# valves_card.net
KiCad netlist of a schematic drawn in EAGLE
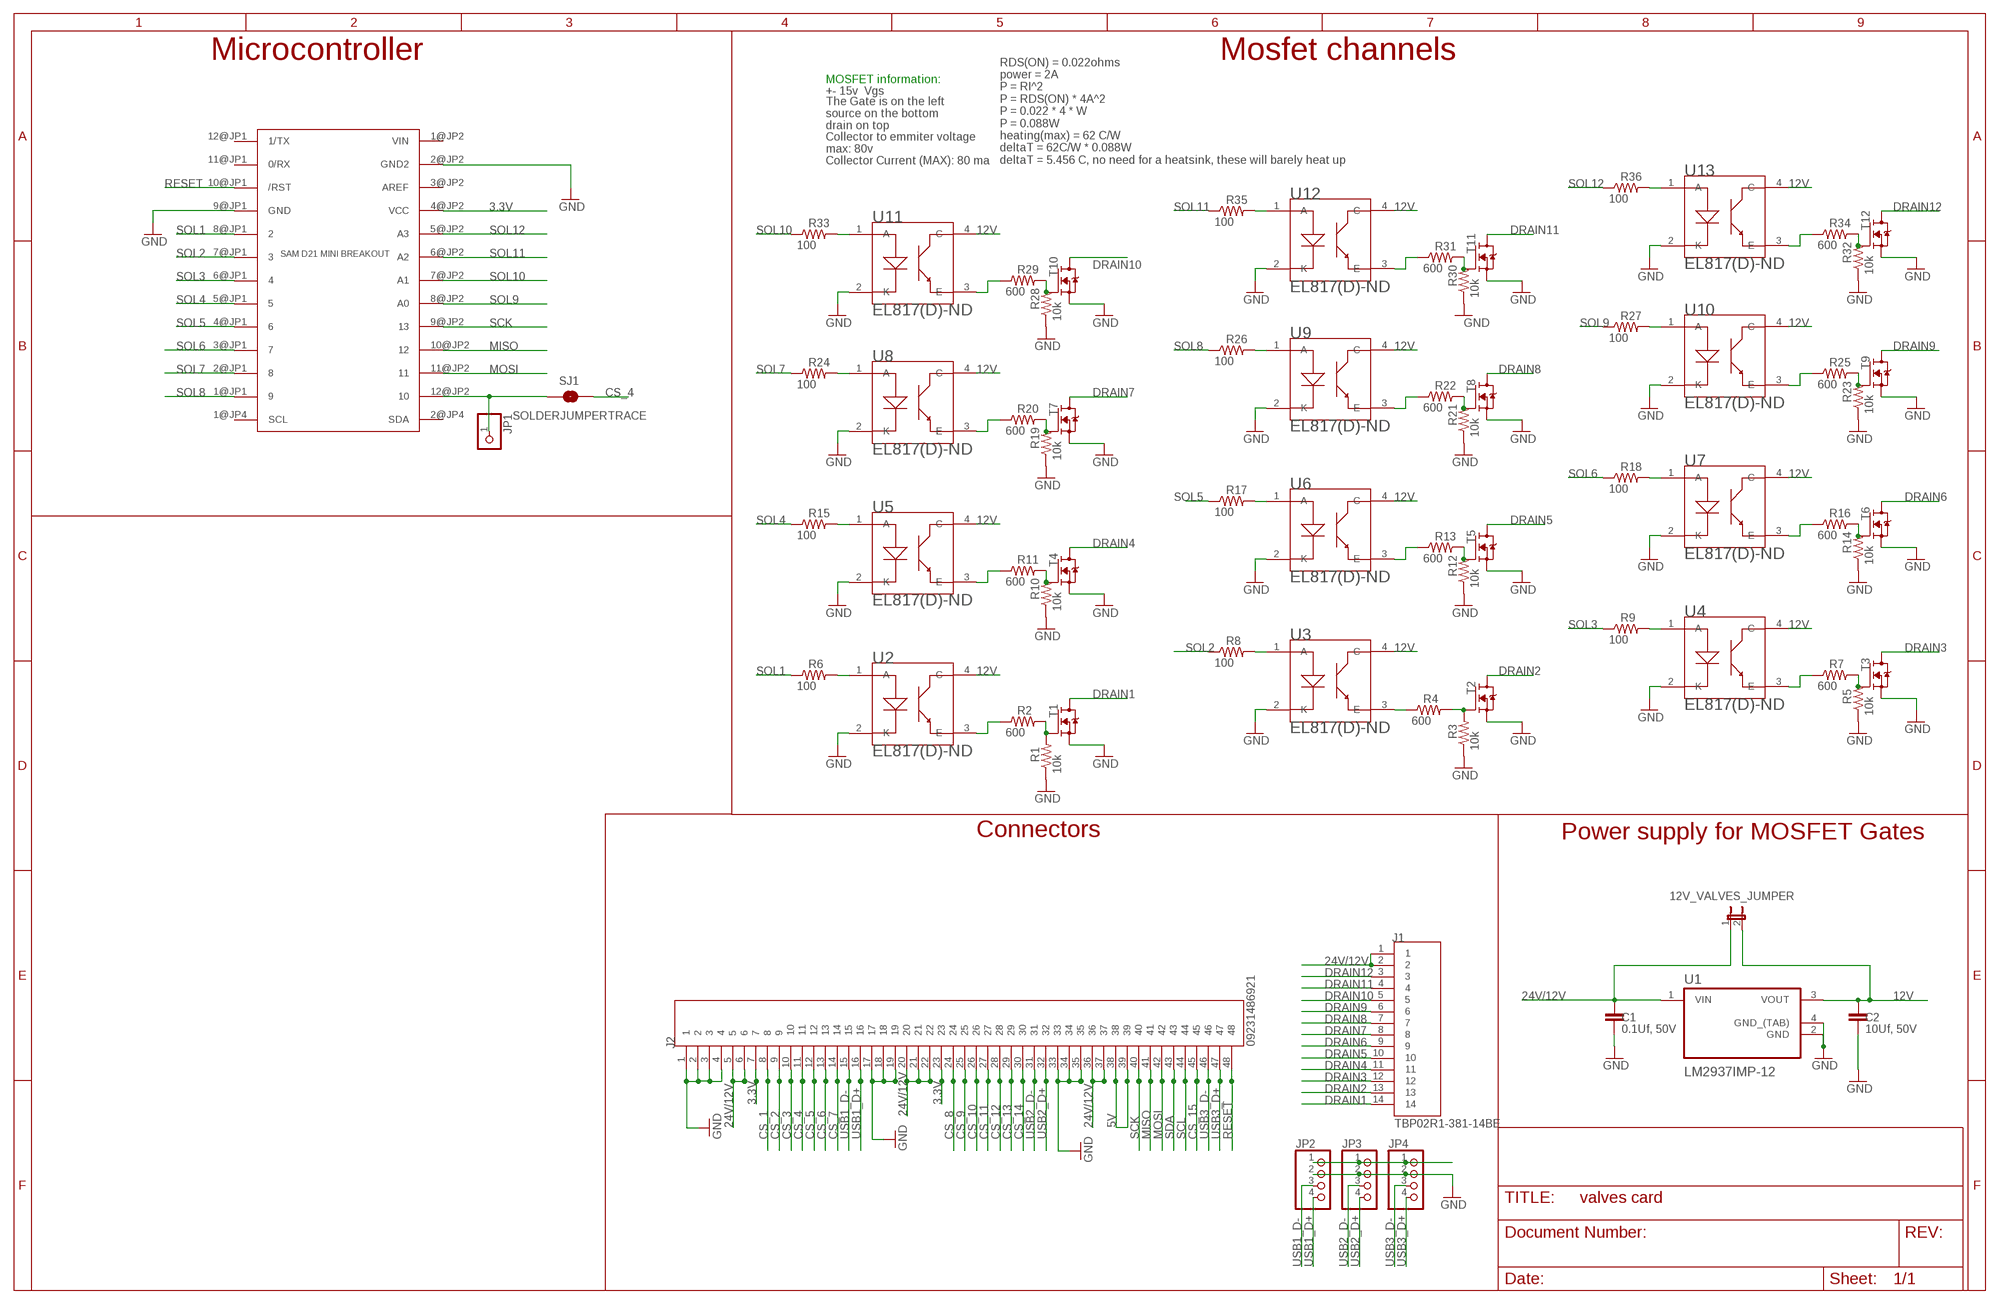
[diagram p0: schematic, sheet 1]

(export (version "E")
  (design (tool "Eeschema 10.0.6"))
  (components
    (comp (ref "12V_VALVES_JUMPER")
      (value "JUMPER-2SMD-NO")
      (footprint "eagle-import:SJ_2S-NO")
      (libsource (lib "eagle-import") (part "JUMPER-2SMD-NO"))
    )
    (comp (ref "C1")
      (value "0.1Uf, 50V")
      (footprint "eagle-import:0805")
      (libsource (lib "eagle-import") (part "CAP0805"))
    )
    (comp (ref "C2")
      (value "10Uf, 50V")
      (footprint "eagle-import:0805")
      (libsource (lib "eagle-import") (part "CAP0805"))
    )
    (comp (ref "J1")
      (value "TBP02R1-381-14BE")
      (footprint "eagle-import:CUI_TBP02R1-381-14BE")
      (libsource (lib "eagle-import") (part "TBP02R1-381-14BE"))
    )
    (comp (ref "J2")
      (value "09231486921")
      (footprint "eagle-import:HARTING_09231486921")
      (libsource (lib "eagle-import") (part "09231486921"))
    )
    (comp (ref "JP1")
      (value "PINHD-1X1")
      (footprint "eagle-import:1X01")
      (libsource (lib "eagle-import") (part "PINHD-1X1"))
    )
    (comp (ref "JP2")
      (value "PINHD-1X4")
      (footprint "eagle-import:1X04")
      (libsource (lib "eagle-import") (part "PINHD-1X4"))
    )
    (comp (ref "JP3")
      (value "PINHD-1X4")
      (footprint "eagle-import:1X04")
      (libsource (lib "eagle-import") (part "PINHD-1X4"))
    )
    (comp (ref "JP4")
      (value "PINHD-1X4")
      (footprint "eagle-import:1X04")
      (libsource (lib "eagle-import") (part "PINHD-1X4"))
    )
    (comp (ref "M2")
      (value "SAM_D21_MINI_BREAKOUT")
      (footprint "eagle-import:JP1_SPARKFUN-SAMD21-MINI-BREAKOUT-V10")
      (libsource (lib "eagle-import") (part "SAM_D21_MINI_BREAKOUT"))
    )
    (comp (ref "R1")
      (value "10k")
      (footprint "eagle-import:0805")
      (libsource (lib "eagle-import") (part "RESISTOR0805-RES"))
    )
    (comp (ref "R2")
      (value "600")
      (footprint "eagle-import:0805")
      (libsource (lib "eagle-import") (part "RESISTOR0805-RES"))
    )
    (comp (ref "R3")
      (value "10k")
      (footprint "eagle-import:0805")
      (libsource (lib "eagle-import") (part "RESISTOR0805-RES"))
    )
    (comp (ref "R4")
      (value "600")
      (footprint "eagle-import:0805")
      (libsource (lib "eagle-import") (part "RESISTOR0805-RES"))
    )
    (comp (ref "R5")
      (value "10k")
      (footprint "eagle-import:0805")
      (libsource (lib "eagle-import") (part "RESISTOR0805-RES"))
    )
    (comp (ref "R6")
      (value "100")
      (footprint "eagle-import:0805")
      (libsource (lib "eagle-import") (part "RESISTOR0805-RES"))
    )
    (comp (ref "R7")
      (value "600")
      (footprint "eagle-import:0805")
      (libsource (lib "eagle-import") (part "RESISTOR0805-RES"))
    )
    (comp (ref "R8")
      (value "100")
      (footprint "eagle-import:0805")
      (libsource (lib "eagle-import") (part "RESISTOR0805-RES"))
    )
    (comp (ref "R9")
      (value "100")
      (footprint "eagle-import:0805")
      (libsource (lib "eagle-import") (part "RESISTOR0805-RES"))
    )
    (comp (ref "R10")
      (value "10k")
      (footprint "eagle-import:0805")
      (libsource (lib "eagle-import") (part "RESISTOR0805-RES"))
    )
    (comp (ref "R11")
      (value "600")
      (footprint "eagle-import:0805")
      (libsource (lib "eagle-import") (part "RESISTOR0805-RES"))
    )
    (comp (ref "R12")
      (value "10k")
      (footprint "eagle-import:0805")
      (libsource (lib "eagle-import") (part "RESISTOR0805-RES"))
    )
    (comp (ref "R13")
      (value "600")
      (footprint "eagle-import:0805")
      (libsource (lib "eagle-import") (part "RESISTOR0805-RES"))
    )
    (comp (ref "R14")
      (value "10k")
      (footprint "eagle-import:0805")
      (libsource (lib "eagle-import") (part "RESISTOR0805-RES"))
    )
    (comp (ref "R15")
      (value "100")
      (footprint "eagle-import:0805")
      (libsource (lib "eagle-import") (part "RESISTOR0805-RES"))
    )
    (comp (ref "R16")
      (value "600")
      (footprint "eagle-import:0805")
      (libsource (lib "eagle-import") (part "RESISTOR0805-RES"))
    )
    (comp (ref "R17")
      (value "100")
      (footprint "eagle-import:0805")
      (libsource (lib "eagle-import") (part "RESISTOR0805-RES"))
    )
    (comp (ref "R18")
      (value "100")
      (footprint "eagle-import:0805")
      (libsource (lib "eagle-import") (part "RESISTOR0805-RES"))
    )
    (comp (ref "R19")
      (value "10k")
      (footprint "eagle-import:0805")
      (libsource (lib "eagle-import") (part "RESISTOR0805-RES"))
    )
    (comp (ref "R20")
      (value "600")
      (footprint "eagle-import:0805")
      (libsource (lib "eagle-import") (part "RESISTOR0805-RES"))
    )
    (comp (ref "R21")
      (value "10k")
      (footprint "eagle-import:0805")
      (libsource (lib "eagle-import") (part "RESISTOR0805-RES"))
    )
    (comp (ref "R22")
      (value "600")
      (footprint "eagle-import:0805")
      (libsource (lib "eagle-import") (part "RESISTOR0805-RES"))
    )
    (comp (ref "R23")
      (value "10k")
      (footprint "eagle-import:0805")
      (libsource (lib "eagle-import") (part "RESISTOR0805-RES"))
    )
    (comp (ref "R24")
      (value "100")
      (footprint "eagle-import:0805")
      (libsource (lib "eagle-import") (part "RESISTOR0805-RES"))
    )
    (comp (ref "R25")
      (value "600")
      (footprint "eagle-import:0805")
      (libsource (lib "eagle-import") (part "RESISTOR0805-RES"))
    )
    (comp (ref "R26")
      (value "100")
      (footprint "eagle-import:0805")
      (libsource (lib "eagle-import") (part "RESISTOR0805-RES"))
    )
    (comp (ref "R27")
      (value "100")
      (footprint "eagle-import:0805")
      (libsource (lib "eagle-import") (part "RESISTOR0805-RES"))
    )
    (comp (ref "R28")
      (value "10k")
      (footprint "eagle-import:0805")
      (libsource (lib "eagle-import") (part "RESISTOR0805-RES"))
    )
    (comp (ref "R29")
      (value "600")
      (footprint "eagle-import:0805")
      (libsource (lib "eagle-import") (part "RESISTOR0805-RES"))
    )
    (comp (ref "R30")
      (value "10k")
      (footprint "eagle-import:0805")
      (libsource (lib "eagle-import") (part "RESISTOR0805-RES"))
    )
    (comp (ref "R31")
      (value "600")
      (footprint "eagle-import:0805")
      (libsource (lib "eagle-import") (part "RESISTOR0805-RES"))
    )
    (comp (ref "R32")
      (value "10k")
      (footprint "eagle-import:0805")
      (libsource (lib "eagle-import") (part "RESISTOR0805-RES"))
    )
    (comp (ref "R33")
      (value "100")
      (footprint "eagle-import:0805")
      (libsource (lib "eagle-import") (part "RESISTOR0805-RES"))
    )
    (comp (ref "R34")
      (value "600")
      (footprint "eagle-import:0805")
      (libsource (lib "eagle-import") (part "RESISTOR0805-RES"))
    )
    (comp (ref "R35")
      (value "100")
      (footprint "eagle-import:0805")
      (libsource (lib "eagle-import") (part "RESISTOR0805-RES"))
    )
    (comp (ref "R36")
      (value "100")
      (footprint "eagle-import:0805")
      (libsource (lib "eagle-import") (part "RESISTOR0805-RES"))
    )
    (comp (ref "SJ1")
      (value "SOLDERJUMPERTRACE")
      (footprint "eagle-import:SJ_2S-TRACE")
      (libsource (lib "eagle-import") (part "SOLDERJUMPERTRACE"))
    )
    (comp (ref "T1")
      (value "IRLZ44NSTRLPBF")
      (footprint "eagle-import:DPAK_TO252")
      (libsource (lib "eagle-import") (part "BUK9214-30A-118-DPAK"))
    )
    (comp (ref "T2")
      (value "IRLZ44NSTRLPBF")
      (footprint "eagle-import:DPAK_TO252")
      (libsource (lib "eagle-import") (part "BUK9214-30A-118-DPAK"))
    )
    (comp (ref "T3")
      (value "IRLZ44NSTRLPBF")
      (footprint "eagle-import:DPAK_TO252")
      (libsource (lib "eagle-import") (part "BUK9214-30A-118-DPAK"))
    )
    (comp (ref "T4")
      (value "IRLZ44NSTRLPBF")
      (footprint "eagle-import:DPAK_TO252")
      (libsource (lib "eagle-import") (part "BUK9214-30A-118-DPAK"))
    )
    (comp (ref "T5")
      (value "IRLZ44NSTRLPBF")
      (footprint "eagle-import:DPAK_TO252")
      (libsource (lib "eagle-import") (part "BUK9214-30A-118-DPAK"))
    )
    (comp (ref "T6")
      (value "IRLZ44NSTRLPBF")
      (footprint "eagle-import:DPAK_TO252")
      (libsource (lib "eagle-import") (part "BUK9214-30A-118-DPAK"))
    )
    (comp (ref "T7")
      (value "IRLZ44NSTRLPBF")
      (footprint "eagle-import:DPAK_TO252")
      (libsource (lib "eagle-import") (part "BUK9214-30A-118-DPAK"))
    )
    (comp (ref "T8")
      (value "IRLZ44NSTRLPBF")
      (footprint "eagle-import:DPAK_TO252")
      (libsource (lib "eagle-import") (part "BUK9214-30A-118-DPAK"))
    )
    (comp (ref "T9")
      (value "IRLZ44NSTRLPBF")
      (footprint "eagle-import:DPAK_TO252")
      (libsource (lib "eagle-import") (part "BUK9214-30A-118-DPAK"))
    )
    (comp (ref "T10")
      (value "IRLZ44NSTRLPBF")
      (footprint "eagle-import:DPAK_TO252")
      (libsource (lib "eagle-import") (part "BUK9214-30A-118-DPAK"))
    )
    (comp (ref "T11")
      (value "IRLZ44NSTRLPBF")
      (footprint "eagle-import:DPAK_TO252")
      (libsource (lib "eagle-import") (part "BUK9214-30A-118-DPAK"))
    )
    (comp (ref "T12")
      (value "IRLZ44NSTRLPBF")
      (footprint "eagle-import:DPAK_TO252")
      (libsource (lib "eagle-import") (part "BUK9214-30A-118-DPAK"))
    )
    (comp (ref "U1")
      (value "LM2937IMP-12")
      (footprint "eagle-import:SOT230P700X180-4N")
      (libsource (lib "eagle-import") (part "LM2937IMP-12"))
    )
    (comp (ref "U2")
      (value "EL817(D)-ND")
      (footprint "eagle-import:DIP4")
      (libsource (lib "eagle-import") (part "EL817(D)"))
    )
    (comp (ref "U3")
      (value "EL817(D)-ND")
      (footprint "eagle-import:DIP4")
      (libsource (lib "eagle-import") (part "EL817(D)"))
    )
    (comp (ref "U4")
      (value "EL817(D)-ND")
      (footprint "eagle-import:DIP4")
      (libsource (lib "eagle-import") (part "EL817(D)"))
    )
    (comp (ref "U5")
      (value "EL817(D)-ND")
      (footprint "eagle-import:DIP4")
      (libsource (lib "eagle-import") (part "EL817(D)"))
    )
    (comp (ref "U6")
      (value "EL817(D)-ND")
      (footprint "eagle-import:DIP4")
      (libsource (lib "eagle-import") (part "EL817(D)"))
    )
    (comp (ref "U7")
      (value "EL817(D)-ND")
      (footprint "eagle-import:DIP4")
      (libsource (lib "eagle-import") (part "EL817(D)"))
    )
    (comp (ref "U8")
      (value "EL817(D)-ND")
      (footprint "eagle-import:DIP4")
      (libsource (lib "eagle-import") (part "EL817(D)"))
    )
    (comp (ref "U9")
      (value "EL817(D)-ND")
      (footprint "eagle-import:DIP4")
      (libsource (lib "eagle-import") (part "EL817(D)"))
    )
    (comp (ref "U10")
      (value "EL817(D)-ND")
      (footprint "eagle-import:DIP4")
      (libsource (lib "eagle-import") (part "EL817(D)"))
    )
    (comp (ref "U11")
      (value "EL817(D)-ND")
      (footprint "eagle-import:DIP4")
      (libsource (lib "eagle-import") (part "EL817(D)"))
    )
    (comp (ref "U12")
      (value "EL817(D)-ND")
      (footprint "eagle-import:DIP4")
      (libsource (lib "eagle-import") (part "EL817(D)"))
    )
    (comp (ref "U13")
      (value "EL817(D)-ND")
      (footprint "eagle-import:DIP4")
      (libsource (lib "eagle-import") (part "EL817(D)"))
    )
  )
  (nets
    (net (code "1") (name "/3.3V") (class "Default")
      (node (ref "J2") (pin "23") (pinfunction "23_23") (pintype "passive"))
      (node (ref "J2") (pin "7") (pinfunction "7_7") (pintype "passive"))
      (node (ref "M2") (pin "4@JP2") (pinfunction "VCC_4@JP2") (pintype "power_in"))
    )
    (net (code "2") (name "/5V") (class "Default")
      (node (ref "J2") (pin "38") (pinfunction "38_38") (pintype "passive"))
      (node (ref "J2") (pin "39") (pinfunction "39_39") (pintype "passive"))
      (node (ref "JP2") (pin "1") (pinfunction "1_1") (pintype "passive"))
      (node (ref "JP3") (pin "1") (pinfunction "1_1") (pintype "passive"))
      (node (ref "JP4") (pin "1") (pinfunction "1_1") (pintype "passive"))
    )
    (net (code "3") (name "/12V") (class "Default")
      (node (ref "12V_VALVES_JUMPER") (pin "2") (pinfunction "2_2") (pintype "passive"))
      (node (ref "C2") (pin "1") (pinfunction "1_1") (pintype "passive"))
      (node (ref "U1") (pin "3") (pinfunction "VOUT_3") (pintype "output"))
      (node (ref "U10") (pin "4") (pinfunction "C_4") (pintype "passive"))
      (node (ref "U11") (pin "4") (pinfunction "C_4") (pintype "passive"))
      (node (ref "U12") (pin "4") (pinfunction "C_4") (pintype "passive"))
      (node (ref "U13") (pin "4") (pinfunction "C_4") (pintype "passive"))
      (node (ref "U2") (pin "4") (pinfunction "C_4") (pintype "passive"))
      (node (ref "U3") (pin "4") (pinfunction "C_4") (pintype "passive"))
      (node (ref "U4") (pin "4") (pinfunction "C_4") (pintype "passive"))
      (node (ref "U5") (pin "4") (pinfunction "C_4") (pintype "passive"))
      (node (ref "U6") (pin "4") (pinfunction "C_4") (pintype "passive"))
      (node (ref "U7") (pin "4") (pinfunction "C_4") (pintype "passive"))
      (node (ref "U8") (pin "4") (pinfunction "C_4") (pintype "passive"))
      (node (ref "U9") (pin "4") (pinfunction "C_4") (pintype "passive"))
    )
    (net (code "4") (name "/24V{slash}12V") (class "Default")
      (node (ref "12V_VALVES_JUMPER") (pin "1") (pinfunction "1_1") (pintype "passive"))
      (node (ref "C1") (pin "1") (pinfunction "1_1") (pintype "passive"))
      (node (ref "J1") (pin "1") (pinfunction "1_1") (pintype "passive"))
      (node (ref "J1") (pin "2") (pinfunction "2_2") (pintype "passive"))
      (node (ref "J2") (pin "20") (pinfunction "20_20") (pintype "passive"))
      (node (ref "J2") (pin "21") (pinfunction "21_21") (pintype "passive"))
      (node (ref "J2") (pin "22") (pinfunction "22_22") (pintype "passive"))
      (node (ref "J2") (pin "36") (pinfunction "36_36") (pintype "passive"))
      (node (ref "J2") (pin "37") (pinfunction "37_37") (pintype "passive"))
      (node (ref "J2") (pin "5") (pinfunction "5_5") (pintype "passive"))
      (node (ref "J2") (pin "6") (pinfunction "6_6") (pintype "passive"))
      (node (ref "U1") (pin "1") (pinfunction "VIN_1") (pintype "input"))
    )
    (net (code "5") (name "/AREF") (class "Default")
      (node (ref "M2") (pin "3@JP2") (pinfunction "AREF_3@JP2") (pintype "power_in"))
    )
    (net (code "6") (name "/CS_1") (class "Default")
      (node (ref "J2") (pin "8") (pinfunction "8_8") (pintype "passive"))
    )
    (net (code "7") (name "/CS_2") (class "Default")
      (node (ref "J2") (pin "9") (pinfunction "9_9") (pintype "passive"))
    )
    (net (code "8") (name "/CS_3") (class "Default")
      (node (ref "J2") (pin "10") (pinfunction "10_10") (pintype "passive"))
    )
    (net (code "9") (name "/CS_4") (class "Default")
      (node (ref "J2") (pin "11") (pinfunction "11_11") (pintype "passive"))
      (node (ref "SJ1") (pin "2") (pinfunction "2_2") (pintype "passive"))
    )
    (net (code "10") (name "/CS_5") (class "Default")
      (node (ref "J2") (pin "12") (pinfunction "12_12") (pintype "passive"))
    )
    (net (code "11") (name "/CS_6") (class "Default")
      (node (ref "J2") (pin "13") (pinfunction "13_13") (pintype "passive"))
    )
    (net (code "12") (name "/CS_7") (class "Default")
      (node (ref "J2") (pin "14") (pinfunction "14_14") (pintype "passive"))
    )
    (net (code "13") (name "/CS_8") (class "Default")
      (node (ref "J2") (pin "24") (pinfunction "24_24") (pintype "passive"))
    )
    (net (code "14") (name "/CS_9") (class "Default")
      (node (ref "J2") (pin "25") (pinfunction "25_25") (pintype "passive"))
    )
    (net (code "15") (name "/CS_10") (class "Default")
      (node (ref "J2") (pin "26") (pinfunction "26_26") (pintype "passive"))
    )
    (net (code "16") (name "/CS_11") (class "Default")
      (node (ref "J2") (pin "27") (pinfunction "27_27") (pintype "passive"))
    )
    (net (code "17") (name "/CS_12") (class "Default")
      (node (ref "J2") (pin "28") (pinfunction "28_28") (pintype "passive"))
    )
    (net (code "18") (name "/CS_13") (class "Default")
      (node (ref "J2") (pin "29") (pinfunction "29_29") (pintype "passive"))
    )
    (net (code "19") (name "/CS_14") (class "Default")
      (node (ref "J2") (pin "30") (pinfunction "30_30") (pintype "passive"))
    )
    (net (code "20") (name "/CS_15") (class "Default")
      (node (ref "J2") (pin "45") (pinfunction "45_45") (pintype "passive"))
    )
    (net (code "21") (name "/DRAIN1") (class "Default")
      (node (ref "J1") (pin "14") (pinfunction "14_14") (pintype "passive"))
      (node (ref "T1") (pin "2") (pinfunction "D_2") (pintype "passive"))
    )
    (net (code "22") (name "/DRAIN2") (class "Default")
      (node (ref "J1") (pin "13") (pinfunction "13_13") (pintype "passive"))
      (node (ref "T2") (pin "2") (pinfunction "D_2") (pintype "passive"))
    )
    (net (code "23") (name "/DRAIN3") (class "Default")
      (node (ref "J1") (pin "12") (pinfunction "12_12") (pintype "passive"))
      (node (ref "T3") (pin "2") (pinfunction "D_2") (pintype "passive"))
    )
    (net (code "24") (name "/DRAIN4") (class "Default")
      (node (ref "J1") (pin "11") (pinfunction "11_11") (pintype "passive"))
      (node (ref "T4") (pin "2") (pinfunction "D_2") (pintype "passive"))
    )
    (net (code "25") (name "/DRAIN5") (class "Default")
      (node (ref "J1") (pin "10") (pinfunction "10_10") (pintype "passive"))
      (node (ref "T5") (pin "2") (pinfunction "D_2") (pintype "passive"))
    )
    (net (code "26") (name "/DRAIN6") (class "Default")
      (node (ref "J1") (pin "9") (pinfunction "9_9") (pintype "passive"))
      (node (ref "T6") (pin "2") (pinfunction "D_2") (pintype "passive"))
    )
    (net (code "27") (name "/DRAIN7") (class "Default")
      (node (ref "J1") (pin "8") (pinfunction "8_8") (pintype "passive"))
      (node (ref "T7") (pin "2") (pinfunction "D_2") (pintype "passive"))
    )
    (net (code "28") (name "/DRAIN8") (class "Default")
      (node (ref "J1") (pin "7") (pinfunction "7_7") (pintype "passive"))
      (node (ref "T8") (pin "2") (pinfunction "D_2") (pintype "passive"))
    )
    (net (code "29") (name "/DRAIN9") (class "Default")
      (node (ref "J1") (pin "6") (pinfunction "6_6") (pintype "passive"))
      (node (ref "T9") (pin "2") (pinfunction "D_2") (pintype "passive"))
    )
    (net (code "30") (name "/DRAIN10") (class "Default")
      (node (ref "J1") (pin "5") (pinfunction "5_5") (pintype "passive"))
      (node (ref "T10") (pin "2") (pinfunction "D_2") (pintype "passive"))
    )
    (net (code "31") (name "/DRAIN11") (class "Default")
      (node (ref "J1") (pin "4") (pinfunction "4_4") (pintype "passive"))
      (node (ref "T11") (pin "2") (pinfunction "D_2") (pintype "passive"))
    )
    (net (code "32") (name "/DRAIN12") (class "Default")
      (node (ref "J1") (pin "3") (pinfunction "3_3") (pintype "passive"))
      (node (ref "T12") (pin "2") (pinfunction "D_2") (pintype "passive"))
    )
    (net (code "33") (name "/MISO") (class "Default")
      (node (ref "J2") (pin "41") (pinfunction "41_41") (pintype "passive"))
      (node (ref "M2") (pin "10@JP2") (pinfunction "12_10@JP2") (pintype "bidirectional"))
    )
    (net (code "34") (name "/MOSI") (class "Default")
      (node (ref "J2") (pin "42") (pinfunction "42_42") (pintype "passive"))
      (node (ref "M2") (pin "11@JP2") (pinfunction "11_11@JP2") (pintype "bidirectional"))
    )
    (net (code "35") (name "/RESET") (class "Default")
      (node (ref "J2") (pin "48") (pinfunction "48_48") (pintype "passive"))
      (node (ref "M2") (pin "10@JP1") (pinfunction "/RST_10@JP1") (pintype "input"))
    )
    (net (code "36") (name "/SCK") (class "Default")
      (node (ref "J2") (pin "40") (pinfunction "40_40") (pintype "passive"))
      (node (ref "M2") (pin "9@JP2") (pinfunction "13_9@JP2") (pintype "bidirectional"))
    )
    (net (code "37") (name "/SCL") (class "Default")
      (node (ref "J2") (pin "44") (pinfunction "44_44") (pintype "passive"))
    )
    (net (code "38") (name "/SDA") (class "Default")
      (node (ref "J2") (pin "43") (pinfunction "43_43") (pintype "passive"))
    )
    (net (code "39") (name "/SOL1") (class "Default")
      (node (ref "M2") (pin "8@JP1") (pinfunction "2_8@JP1") (pintype "bidirectional"))
      (node (ref "R6") (pin "1") (pinfunction "1_1") (pintype "passive"))
    )
    (net (code "40") (name "/SOL2") (class "Default")
      (node (ref "M2") (pin "7@JP1") (pinfunction "3_7@JP1") (pintype "bidirectional"))
      (node (ref "R8") (pin "1") (pinfunction "1_1") (pintype "passive"))
    )
    (net (code "41") (name "/SOL3") (class "Default")
      (node (ref "M2") (pin "6@JP1") (pinfunction "4_6@JP1") (pintype "bidirectional"))
      (node (ref "R9") (pin "1") (pinfunction "1_1") (pintype "passive"))
    )
    (net (code "42") (name "/SOL4") (class "Default")
      (node (ref "M2") (pin "5@JP1") (pinfunction "5_5@JP1") (pintype "bidirectional"))
      (node (ref "R15") (pin "1") (pinfunction "1_1") (pintype "passive"))
    )
    (net (code "43") (name "/SOL5") (class "Default")
      (node (ref "M2") (pin "4@JP1") (pinfunction "6_4@JP1") (pintype "bidirectional"))
      (node (ref "R17") (pin "1") (pinfunction "1_1") (pintype "passive"))
    )
    (net (code "44") (name "/SOL6") (class "Default")
      (node (ref "M2") (pin "3@JP1") (pinfunction "7_3@JP1") (pintype "bidirectional"))
      (node (ref "R18") (pin "1") (pinfunction "1_1") (pintype "passive"))
    )
    (net (code "45") (name "/SOL7") (class "Default")
      (node (ref "M2") (pin "2@JP1") (pinfunction "8_2@JP1") (pintype "bidirectional"))
      (node (ref "R24") (pin "1") (pinfunction "1_1") (pintype "passive"))
    )
    (net (code "46") (name "/SOL8") (class "Default")
      (node (ref "M2") (pin "1@JP1") (pinfunction "9_1@JP1") (pintype "bidirectional"))
      (node (ref "R26") (pin "1") (pinfunction "1_1") (pintype "passive"))
    )
    (net (code "47") (name "/SOL9") (class "Default")
      (node (ref "M2") (pin "8@JP2") (pinfunction "A0_8@JP2") (pintype "bidirectional"))
      (node (ref "R27") (pin "1") (pinfunction "1_1") (pintype "passive"))
    )
    (net (code "48") (name "/SOL10") (class "Default")
      (node (ref "M2") (pin "7@JP2") (pinfunction "A1_7@JP2") (pintype "bidirectional"))
      (node (ref "R33") (pin "1") (pinfunction "1_1") (pintype "passive"))
    )
    (net (code "49") (name "/SOL11") (class "Default")
      (node (ref "M2") (pin "6@JP2") (pinfunction "A2_6@JP2") (pintype "bidirectional"))
      (node (ref "R35") (pin "1") (pinfunction "1_1") (pintype "passive"))
    )
    (net (code "50") (name "/SOL12") (class "Default")
      (node (ref "M2") (pin "5@JP2") (pinfunction "A3_5@JP2") (pintype "bidirectional"))
      (node (ref "R36") (pin "1") (pinfunction "1_1") (pintype "passive"))
    )
    (net (code "51") (name "/USB1_D+") (class "Default")
      (node (ref "J2") (pin "16") (pinfunction "16_16") (pintype "passive"))
      (node (ref "JP2") (pin "4") (pinfunction "4_4") (pintype "passive"))
    )
    (net (code "52") (name "/USB1_D-") (class "Default")
      (node (ref "J2") (pin "15") (pinfunction "15_15") (pintype "passive"))
      (node (ref "JP2") (pin "3") (pinfunction "3_3") (pintype "passive"))
    )
    (net (code "53") (name "/USB2_D+") (class "Default")
      (node (ref "J2") (pin "32") (pinfunction "32_32") (pintype "passive"))
      (node (ref "JP3") (pin "4") (pinfunction "4_4") (pintype "passive"))
    )
    (net (code "54") (name "/USB2_D-") (class "Default")
      (node (ref "J2") (pin "31") (pinfunction "31_31") (pintype "passive"))
      (node (ref "JP3") (pin "3") (pinfunction "3_3") (pintype "passive"))
    )
    (net (code "55") (name "/USB3_D+") (class "Default")
      (node (ref "J2") (pin "47") (pinfunction "47_47") (pintype "passive"))
      (node (ref "JP4") (pin "4") (pinfunction "4_4") (pintype "passive"))
    )
    (net (code "56") (name "/USB3_D-") (class "Default")
      (node (ref "J2") (pin "46") (pinfunction "46_46") (pintype "passive"))
      (node (ref "JP4") (pin "3") (pinfunction "3_3") (pintype "passive"))
    )
    (net (code "57") (name "/VIN") (class "Default")
      (node (ref "M2") (pin "1@JP2") (pinfunction "VIN_1@JP2") (pintype "power_in"))
    )
    (net (code "58") (name "GND") (class "Default")
      (node (ref "C1") (pin "2") (pinfunction "2_2") (pintype "passive"))
      (node (ref "C2") (pin "2") (pinfunction "2_2") (pintype "passive"))
      (node (ref "J2") (pin "1") (pinfunction "1_1") (pintype "passive"))
      (node (ref "J2") (pin "17") (pinfunction "17_17") (pintype "passive"))
      (node (ref "J2") (pin "18") (pinfunction "18_18") (pintype "passive"))
      (node (ref "J2") (pin "19") (pinfunction "19_19") (pintype "passive"))
      (node (ref "J2") (pin "2") (pinfunction "2_2") (pintype "passive"))
      (node (ref "J2") (pin "3") (pinfunction "3_3") (pintype "passive"))
      (node (ref "J2") (pin "33") (pinfunction "33_33") (pintype "passive"))
      (node (ref "J2") (pin "34") (pinfunction "34_34") (pintype "passive"))
      (node (ref "J2") (pin "35") (pinfunction "35_35") (pintype "passive"))
      (node (ref "J2") (pin "4") (pinfunction "4_4") (pintype "passive"))
      (node (ref "JP2") (pin "2") (pinfunction "2_2") (pintype "passive"))
      (node (ref "JP3") (pin "2") (pinfunction "2_2") (pintype "passive"))
      (node (ref "JP4") (pin "2") (pinfunction "2_2") (pintype "passive"))
      (node (ref "M2") (pin "2@JP2") (pinfunction "GND2_2@JP2") (pintype "power_in"))
      (node (ref "M2") (pin "9@JP1") (pinfunction "GND_9@JP1") (pintype "power_in"))
      (node (ref "R1") (pin "1") (pinfunction "1_1") (pintype "passive"))
      (node (ref "R10") (pin "1") (pinfunction "1_1") (pintype "passive"))
      (node (ref "R12") (pin "1") (pinfunction "1_1") (pintype "passive"))
      (node (ref "R14") (pin "1") (pinfunction "1_1") (pintype "passive"))
      (node (ref "R19") (pin "1") (pinfunction "1_1") (pintype "passive"))
      (node (ref "R21") (pin "1") (pinfunction "1_1") (pintype "passive"))
      (node (ref "R23") (pin "1") (pinfunction "1_1") (pintype "passive"))
      (node (ref "R28") (pin "1") (pinfunction "1_1") (pintype "passive"))
      (node (ref "R3") (pin "1") (pinfunction "1_1") (pintype "passive"))
      (node (ref "R30") (pin "1") (pinfunction "1_1") (pintype "passive"))
      (node (ref "R32") (pin "1") (pinfunction "1_1") (pintype "passive"))
      (node (ref "R5") (pin "1") (pinfunction "1_1") (pintype "passive"))
      (node (ref "T1") (pin "3") (pinfunction "S_3") (pintype "passive"))
      (node (ref "T10") (pin "3") (pinfunction "S_3") (pintype "passive"))
      (node (ref "T11") (pin "3") (pinfunction "S_3") (pintype "passive"))
      (node (ref "T12") (pin "3") (pinfunction "S_3") (pintype "passive"))
      (node (ref "T2") (pin "3") (pinfunction "S_3") (pintype "passive"))
      (node (ref "T3") (pin "3") (pinfunction "S_3") (pintype "passive"))
      (node (ref "T4") (pin "3") (pinfunction "S_3") (pintype "passive"))
      (node (ref "T5") (pin "3") (pinfunction "S_3") (pintype "passive"))
      (node (ref "T6") (pin "3") (pinfunction "S_3") (pintype "passive"))
      (node (ref "T7") (pin "3") (pinfunction "S_3") (pintype "passive"))
      (node (ref "T8") (pin "3") (pinfunction "S_3") (pintype "passive"))
      (node (ref "T9") (pin "3") (pinfunction "S_3") (pintype "passive"))
      (node (ref "U1") (pin "2") (pinfunction "GND_2") (pintype "power_in"))
      (node (ref "U1") (pin "4") (pinfunction "GND_(TAB)_4") (pintype "power_in"))
      (node (ref "U10") (pin "2") (pinfunction "K_2") (pintype "passive"))
      (node (ref "U11") (pin "2") (pinfunction "K_2") (pintype "passive"))
      (node (ref "U12") (pin "2") (pinfunction "K_2") (pintype "passive"))
      (node (ref "U13") (pin "2") (pinfunction "K_2") (pintype "passive"))
      (node (ref "U2") (pin "2") (pinfunction "K_2") (pintype "passive"))
      (node (ref "U3") (pin "2") (pinfunction "K_2") (pintype "passive"))
      (node (ref "U4") (pin "2") (pinfunction "K_2") (pintype "passive"))
      (node (ref "U5") (pin "2") (pinfunction "K_2") (pintype "passive"))
      (node (ref "U6") (pin "2") (pinfunction "K_2") (pintype "passive"))
      (node (ref "U7") (pin "2") (pinfunction "K_2") (pintype "passive"))
      (node (ref "U8") (pin "2") (pinfunction "K_2") (pintype "passive"))
      (node (ref "U9") (pin "2") (pinfunction "K_2") (pintype "passive"))
    )
    (net (code "59") (name "Net-(M2-10)") (class "Default")
      (node (ref "JP1") (pin "1") (pinfunction "1_1") (pintype "passive"))
      (node (ref "M2") (pin "12@JP2") (pinfunction "10_12@JP2") (pintype "bidirectional"))
      (node (ref "SJ1") (pin "1") (pinfunction "1_1") (pintype "passive"))
    )
    (net (code "60") (name "Net-(T1-G)") (class "Default")
      (node (ref "R1") (pin "2") (pinfunction "2_2") (pintype "passive"))
      (node (ref "R2") (pin "2") (pinfunction "2_2") (pintype "passive"))
      (node (ref "T1") (pin "1") (pinfunction "G_1") (pintype "passive"))
    )
    (net (code "61") (name "Net-(T2-G)") (class "Default")
      (node (ref "R3") (pin "2") (pinfunction "2_2") (pintype "passive"))
      (node (ref "R4") (pin "2") (pinfunction "2_2") (pintype "passive"))
      (node (ref "T2") (pin "1") (pinfunction "G_1") (pintype "passive"))
    )
    (net (code "62") (name "Net-(T3-G)") (class "Default")
      (node (ref "R5") (pin "2") (pinfunction "2_2") (pintype "passive"))
      (node (ref "R7") (pin "2") (pinfunction "2_2") (pintype "passive"))
      (node (ref "T3") (pin "1") (pinfunction "G_1") (pintype "passive"))
    )
    (net (code "63") (name "Net-(T4-G)") (class "Default")
      (node (ref "R10") (pin "2") (pinfunction "2_2") (pintype "passive"))
      (node (ref "R11") (pin "2") (pinfunction "2_2") (pintype "passive"))
      (node (ref "T4") (pin "1") (pinfunction "G_1") (pintype "passive"))
    )
    (net (code "64") (name "Net-(T5-G)") (class "Default")
      (node (ref "R12") (pin "2") (pinfunction "2_2") (pintype "passive"))
      (node (ref "R13") (pin "2") (pinfunction "2_2") (pintype "passive"))
      (node (ref "T5") (pin "1") (pinfunction "G_1") (pintype "passive"))
    )
    (net (code "65") (name "Net-(T6-G)") (class "Default")
      (node (ref "R14") (pin "2") (pinfunction "2_2") (pintype "passive"))
      (node (ref "R16") (pin "2") (pinfunction "2_2") (pintype "passive"))
      (node (ref "T6") (pin "1") (pinfunction "G_1") (pintype "passive"))
    )
    (net (code "66") (name "Net-(T7-G)") (class "Default")
      (node (ref "R19") (pin "2") (pinfunction "2_2") (pintype "passive"))
      (node (ref "R20") (pin "2") (pinfunction "2_2") (pintype "passive"))
      (node (ref "T7") (pin "1") (pinfunction "G_1") (pintype "passive"))
    )
    (net (code "67") (name "Net-(T8-G)") (class "Default")
      (node (ref "R21") (pin "2") (pinfunction "2_2") (pintype "passive"))
      (node (ref "R22") (pin "2") (pinfunction "2_2") (pintype "passive"))
      (node (ref "T8") (pin "1") (pinfunction "G_1") (pintype "passive"))
    )
    (net (code "68") (name "Net-(T9-G)") (class "Default")
      (node (ref "R23") (pin "2") (pinfunction "2_2") (pintype "passive"))
      (node (ref "R25") (pin "2") (pinfunction "2_2") (pintype "passive"))
      (node (ref "T9") (pin "1") (pinfunction "G_1") (pintype "passive"))
    )
    (net (code "69") (name "Net-(T10-G)") (class "Default")
      (node (ref "R28") (pin "2") (pinfunction "2_2") (pintype "passive"))
      (node (ref "R29") (pin "2") (pinfunction "2_2") (pintype "passive"))
      (node (ref "T10") (pin "1") (pinfunction "G_1") (pintype "passive"))
    )
    (net (code "70") (name "Net-(T11-G)") (class "Default")
      (node (ref "R30") (pin "2") (pinfunction "2_2") (pintype "passive"))
      (node (ref "R31") (pin "2") (pinfunction "2_2") (pintype "passive"))
      (node (ref "T11") (pin "1") (pinfunction "G_1") (pintype "passive"))
    )
    (net (code "71") (name "Net-(T12-G)") (class "Default")
      (node (ref "R32") (pin "2") (pinfunction "2_2") (pintype "passive"))
      (node (ref "R34") (pin "2") (pinfunction "2_2") (pintype "passive"))
      (node (ref "T12") (pin "1") (pinfunction "G_1") (pintype "passive"))
    )
    (net (code "72") (name "Net-(U2-A)") (class "Default")
      (node (ref "R6") (pin "2") (pinfunction "2_2") (pintype "passive"))
      (node (ref "U2") (pin "1") (pinfunction "A_1") (pintype "passive"))
    )
    (net (code "73") (name "Net-(U2-E)") (class "Default")
      (node (ref "R2") (pin "1") (pinfunction "1_1") (pintype "passive"))
      (node (ref "U2") (pin "3") (pinfunction "E_3") (pintype "passive"))
    )
    (net (code "74") (name "Net-(U3-A)") (class "Default")
      (node (ref "R8") (pin "2") (pinfunction "2_2") (pintype "passive"))
      (node (ref "U3") (pin "1") (pinfunction "A_1") (pintype "passive"))
    )
    (net (code "75") (name "Net-(U3-E)") (class "Default")
      (node (ref "R4") (pin "1") (pinfunction "1_1") (pintype "passive"))
      (node (ref "U3") (pin "3") (pinfunction "E_3") (pintype "passive"))
    )
    (net (code "76") (name "Net-(U4-A)") (class "Default")
      (node (ref "R9") (pin "2") (pinfunction "2_2") (pintype "passive"))
      (node (ref "U4") (pin "1") (pinfunction "A_1") (pintype "passive"))
    )
    (net (code "77") (name "Net-(U4-E)") (class "Default")
      (node (ref "R7") (pin "1") (pinfunction "1_1") (pintype "passive"))
      (node (ref "U4") (pin "3") (pinfunction "E_3") (pintype "passive"))
    )
    (net (code "78") (name "Net-(U5-A)") (class "Default")
      (node (ref "R15") (pin "2") (pinfunction "2_2") (pintype "passive"))
      (node (ref "U5") (pin "1") (pinfunction "A_1") (pintype "passive"))
    )
    (net (code "79") (name "Net-(U5-E)") (class "Default")
      (node (ref "R11") (pin "1") (pinfunction "1_1") (pintype "passive"))
      (node (ref "U5") (pin "3") (pinfunction "E_3") (pintype "passive"))
    )
    (net (code "80") (name "Net-(U6-A)") (class "Default")
      (node (ref "R17") (pin "2") (pinfunction "2_2") (pintype "passive"))
      (node (ref "U6") (pin "1") (pinfunction "A_1") (pintype "passive"))
    )
    (net (code "81") (name "Net-(U6-E)") (class "Default")
      (node (ref "R13") (pin "1") (pinfunction "1_1") (pintype "passive"))
      (node (ref "U6") (pin "3") (pinfunction "E_3") (pintype "passive"))
    )
    (net (code "82") (name "Net-(U7-A)") (class "Default")
      (node (ref "R18") (pin "2") (pinfunction "2_2") (pintype "passive"))
      (node (ref "U7") (pin "1") (pinfunction "A_1") (pintype "passive"))
    )
    (net (code "83") (name "Net-(U7-E)") (class "Default")
      (node (ref "R16") (pin "1") (pinfunction "1_1") (pintype "passive"))
      (node (ref "U7") (pin "3") (pinfunction "E_3") (pintype "passive"))
    )
    (net (code "84") (name "Net-(U8-A)") (class "Default")
      (node (ref "R24") (pin "2") (pinfunction "2_2") (pintype "passive"))
      (node (ref "U8") (pin "1") (pinfunction "A_1") (pintype "passive"))
    )
    (net (code "85") (name "Net-(U8-E)") (class "Default")
      (node (ref "R20") (pin "1") (pinfunction "1_1") (pintype "passive"))
      (node (ref "U8") (pin "3") (pinfunction "E_3") (pintype "passive"))
    )
    (net (code "86") (name "Net-(U9-A)") (class "Default")
      (node (ref "R26") (pin "2") (pinfunction "2_2") (pintype "passive"))
      (node (ref "U9") (pin "1") (pinfunction "A_1") (pintype "passive"))
    )
    (net (code "87") (name "Net-(U9-E)") (class "Default")
      (node (ref "R22") (pin "1") (pinfunction "1_1") (pintype "passive"))
      (node (ref "U9") (pin "3") (pinfunction "E_3") (pintype "passive"))
    )
    (net (code "88") (name "Net-(U10-A)") (class "Default")
      (node (ref "R27") (pin "2") (pinfunction "2_2") (pintype "passive"))
      (node (ref "U10") (pin "1") (pinfunction "A_1") (pintype "passive"))
    )
    (net (code "89") (name "Net-(U10-E)") (class "Default")
      (node (ref "R25") (pin "1") (pinfunction "1_1") (pintype "passive"))
      (node (ref "U10") (pin "3") (pinfunction "E_3") (pintype "passive"))
    )
    (net (code "90") (name "Net-(U11-A)") (class "Default")
      (node (ref "R33") (pin "2") (pinfunction "2_2") (pintype "passive"))
      (node (ref "U11") (pin "1") (pinfunction "A_1") (pintype "passive"))
    )
    (net (code "91") (name "Net-(U11-E)") (class "Default")
      (node (ref "R29") (pin "1") (pinfunction "1_1") (pintype "passive"))
      (node (ref "U11") (pin "3") (pinfunction "E_3") (pintype "passive"))
    )
    (net (code "92") (name "Net-(U12-A)") (class "Default")
      (node (ref "R35") (pin "2") (pinfunction "2_2") (pintype "passive"))
      (node (ref "U12") (pin "1") (pinfunction "A_1") (pintype "passive"))
    )
    (net (code "93") (name "Net-(U12-E)") (class "Default")
      (node (ref "R31") (pin "1") (pinfunction "1_1") (pintype "passive"))
      (node (ref "U12") (pin "3") (pinfunction "E_3") (pintype "passive"))
    )
    (net (code "94") (name "Net-(U13-A)") (class "Default")
      (node (ref "R36") (pin "2") (pinfunction "2_2") (pintype "passive"))
      (node (ref "U13") (pin "1") (pinfunction "A_1") (pintype "passive"))
    )
    (net (code "95") (name "Net-(U13-E)") (class "Default")
      (node (ref "R34") (pin "1") (pinfunction "1_1") (pintype "passive"))
      (node (ref "U13") (pin "3") (pinfunction "E_3") (pintype "passive"))
    )
    (net (code "96") (name "unconnected-(M2-0{slash}RX-Pad11@JP1)") (class "Default")
      (node (ref "M2") (pin "11@JP1") (pinfunction "0/RX_11@JP1") (pintype "bidirectional"))
    )
    (net (code "97") (name "unconnected-(M2-1{slash}TX-Pad12@JP1)") (class "Default")
      (node (ref "M2") (pin "12@JP1") (pinfunction "1/TX_12@JP1") (pintype "bidirectional"))
    )
    (net (code "98") (name "unconnected-(M2-SCL-Pad1@JP4)") (class "Default")
      (node (ref "M2") (pin "1@JP4") (pinfunction "SCL_1@JP4") (pintype "bidirectional"))
    )
    (net (code "99") (name "unconnected-(M2-SDA-Pad2@JP4)") (class "Default")
      (node (ref "M2") (pin "2@JP4") (pinfunction "SDA_2@JP4") (pintype "bidirectional"))
    )
  )
)
